# LCD12864.net
KiCad netlist of a schematic drawn in Altium Designer
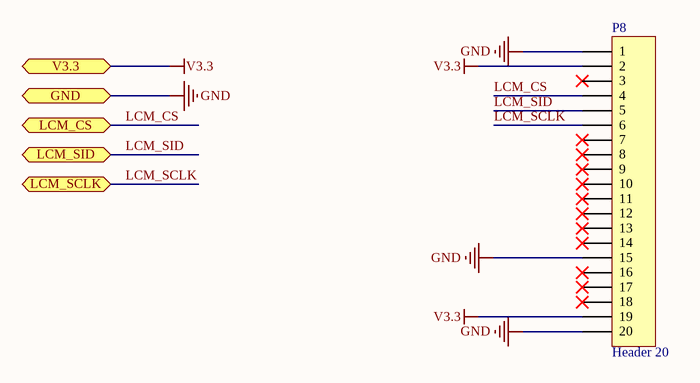
[diagram p0: LCD12864.SchDoc]

(export (version "E")
  (design (tool "Eeschema 10.0.6"))
  (components
    (comp (ref "P8")
      (value "Header 20")
      (footprint "HDR1X20")
      (description "Header, 20-Pin")
      (fields (field (name "PUBLISHER") "Altium Limited"))
      (libsource (lib "Miscellaneous Connectors") (part "Header 20"))
    )
  )
  (nets
    (net (code "1") (name "/LCM_CS") (class "Default")
      (node (ref "P8") (pin "4") (pinfunction "4_4") (pintype "passive"))
    )
    (net (code "2") (name "/LCM_SCLK") (class "Default")
      (node (ref "P8") (pin "6") (pinfunction "6_6") (pintype "passive"))
    )
    (net (code "3") (name "/LCM_SID") (class "Default")
      (node (ref "P8") (pin "5") (pinfunction "5_5") (pintype "passive"))
    )
    (net (code "4") (name "GND") (class "Default")
      (node (ref "P8") (pin "1") (pinfunction "1_1") (pintype "passive"))
      (node (ref "P8") (pin "15") (pinfunction "15_15") (pintype "passive"))
      (node (ref "P8") (pin "20") (pinfunction "20_20") (pintype "passive"))
    )
    (net (code "5") (name "V3.3") (class "Default")
      (node (ref "P8") (pin "19") (pinfunction "19_19") (pintype "passive"))
      (node (ref "P8") (pin "2") (pinfunction "2_2") (pintype "passive"))
    )
    (net (code "6") (name "unconnected-(P8-Pad3)") (class "Default")
      (node (ref "P8") (pin "3") (pinfunction "3_3") (pintype "passive+no_connect"))
    )
    (net (code "7") (name "unconnected-(P8-Pad7)") (class "Default")
      (node (ref "P8") (pin "7") (pinfunction "7_7") (pintype "passive+no_connect"))
    )
    (net (code "8") (name "unconnected-(P8-Pad8)") (class "Default")
      (node (ref "P8") (pin "8") (pinfunction "8_8") (pintype "passive+no_connect"))
    )
    (net (code "9") (name "unconnected-(P8-Pad9)") (class "Default")
      (node (ref "P8") (pin "9") (pinfunction "9_9") (pintype "passive+no_connect"))
    )
    (net (code "10") (name "unconnected-(P8-Pad10)") (class "Default")
      (node (ref "P8") (pin "10") (pinfunction "10_10") (pintype "passive+no_connect"))
    )
    (net (code "11") (name "unconnected-(P8-Pad11)") (class "Default")
      (node (ref "P8") (pin "11") (pinfunction "11_11") (pintype "passive+no_connect"))
    )
    (net (code "12") (name "unconnected-(P8-Pad12)") (class "Default")
      (node (ref "P8") (pin "12") (pinfunction "12_12") (pintype "passive+no_connect"))
    )
    (net (code "13") (name "unconnected-(P8-Pad13)") (class "Default")
      (node (ref "P8") (pin "13") (pinfunction "13_13") (pintype "passive+no_connect"))
    )
    (net (code "14") (name "unconnected-(P8-Pad14)") (class "Default")
      (node (ref "P8") (pin "14") (pinfunction "14_14") (pintype "passive+no_connect"))
    )
    (net (code "15") (name "unconnected-(P8-Pad16)") (class "Default")
      (node (ref "P8") (pin "16") (pinfunction "16_16") (pintype "passive+no_connect"))
    )
    (net (code "16") (name "unconnected-(P8-Pad17)") (class "Default")
      (node (ref "P8") (pin "17") (pinfunction "17_17") (pintype "passive+no_connect"))
    )
    (net (code "17") (name "unconnected-(P8-Pad18)") (class "Default")
      (node (ref "P8") (pin "18") (pinfunction "18_18") (pintype "passive+no_connect"))
    )
  )
)
